# Schematic.net
KiCad netlist of a schematic drawn in EAGLE
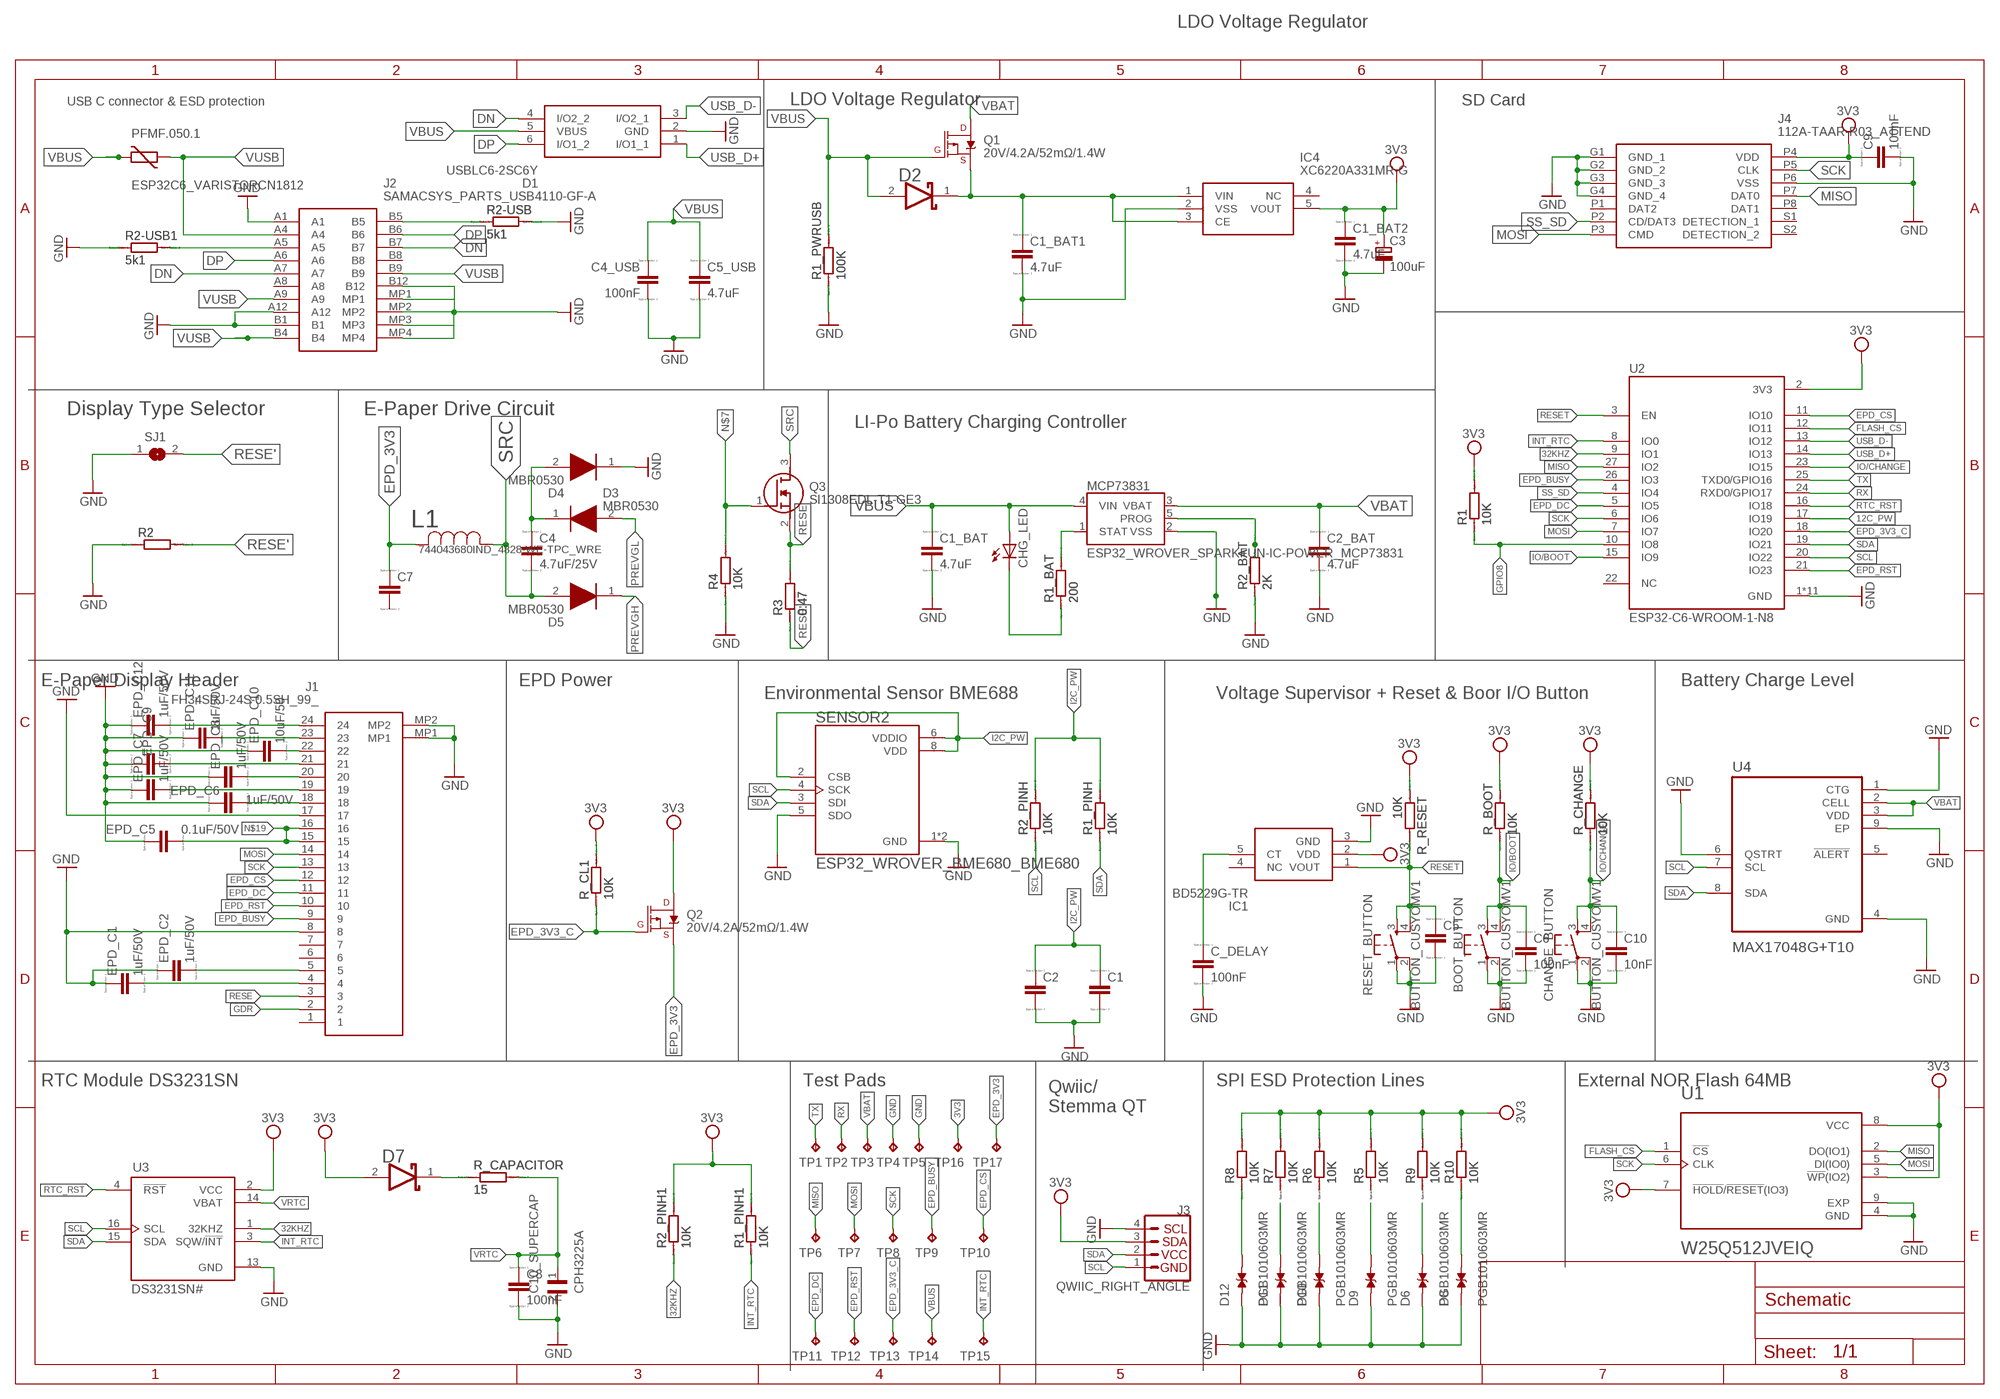
[diagram p0: schematic, sheet 1]

(export (version "E")
  (design (tool "Eeschema 10.0.6"))
  (components
    (comp (ref "BOOT_BUTTON")
      (value "BUTTON_CUSYOMV1")
      (footprint "eagle-import:MYBUTTON")
      (libsource (lib "eagle-import") (part "BUTTON_CUSYOMV1"))
    )
    (comp (ref "C1")
      (value "EAGLE-LTSPICE_CC0402")
      (footprint "eagle-import:EAGLE-LTSPICE_C0402")
      (libsource (lib "eagle-import") (part "EAGLE-LTSPICE_CC0402"))
    )
    (comp (ref "C1_BAT")
      (value "4.7uF")
      (footprint "eagle-import:EAGLE-LTSPICE_C0402")
      (libsource (lib "eagle-import") (part "EAGLE-LTSPICE_CC0402"))
    )
    (comp (ref "C1_BAT1")
      (value "4.7uF")
      (footprint "eagle-import:EAGLE-LTSPICE_C0402")
      (libsource (lib "eagle-import") (part "EAGLE-LTSPICE_CC0402"))
    )
    (comp (ref "C1_BAT2")
      (value "4.7uF")
      (footprint "eagle-import:EAGLE-LTSPICE_C0402")
      (libsource (lib "eagle-import") (part "EAGLE-LTSPICE_CC0402"))
    )
    (comp (ref "C2")
      (value "EAGLE-LTSPICE_CC0402")
      (footprint "eagle-import:EAGLE-LTSPICE_C0402")
      (libsource (lib "eagle-import") (part "EAGLE-LTSPICE_CC0402"))
    )
    (comp (ref "C2_BAT")
      (value "4.7uF")
      (footprint "eagle-import:EAGLE-LTSPICE_C0402")
      (libsource (lib "eagle-import") (part "EAGLE-LTSPICE_CC0402"))
    )
    (comp (ref "C3")
      (value "100uF")
      (footprint "eagle-import:RCL_CT3528")
      (libsource (lib "eagle-import") (part "RCL_CPOL-EUCT3528"))
    )
    (comp (ref "C4")
      (value "4.7uF/25V")
      (footprint "eagle-import:EAGLE-LTSPICE_C0402")
      (libsource (lib "eagle-import") (part "EAGLE-LTSPICE_CC0402"))
    )
    (comp (ref "C4_USB")
      (value "100nF")
      (footprint "eagle-import:EAGLE-LTSPICE_C0402")
      (libsource (lib "eagle-import") (part "EAGLE-LTSPICE_CC0402"))
    )
    (comp (ref "C5")
      (value "EAGLE-LTSPICE_CC0402")
      (footprint "eagle-import:EAGLE-LTSPICE_C0402")
      (libsource (lib "eagle-import") (part "EAGLE-LTSPICE_CC0402"))
    )
    (comp (ref "C5_USB")
      (value "4.7uF")
      (footprint "eagle-import:EAGLE-LTSPICE_C0402")
      (libsource (lib "eagle-import") (part "EAGLE-LTSPICE_CC0402"))
    )
    (comp (ref "C6")
      (value "100nF")
      (footprint "eagle-import:EAGLE-LTSPICE_C0402")
      (libsource (lib "eagle-import") (part "EAGLE-LTSPICE_CC0402"))
    )
    (comp (ref "C7")
      (value "EAGLE-LTSPICE_CC0402")
      (footprint "eagle-import:EAGLE-LTSPICE_C0402")
      (libsource (lib "eagle-import") (part "EAGLE-LTSPICE_CC0402"))
    )
    (comp (ref "C8")
      (value "100nF")
      (footprint "eagle-import:EAGLE-LTSPICE_C0402")
      (libsource (lib "eagle-import") (part "EAGLE-LTSPICE_CC0402"))
    )
    (comp (ref "C9")
      (value "100nF")
      (footprint "eagle-import:EAGLE-LTSPICE_C0402")
      (libsource (lib "eagle-import") (part "EAGLE-LTSPICE_CC0402"))
    )
    (comp (ref "C10")
      (value "10nF")
      (footprint "eagle-import:EAGLE-LTSPICE_C0402")
      (libsource (lib "eagle-import") (part "EAGLE-LTSPICE_CC0402"))
    )
    (comp (ref "C10_SUPERCAP")
      (value "CPH3225A")
      (footprint "eagle-import:CAPCP3225X100N")
      (fields (field (name "MF") "Seiko Instruments"))
      (libsource (lib "eagle-import") (part "CPH3225A"))
    )
    (comp (ref "CHANGE_BUTTON")
      (value "BUTTON_CUSYOMV1")
      (footprint "eagle-import:MYBUTTON")
      (libsource (lib "eagle-import") (part "BUTTON_CUSYOMV1"))
    )
    (comp (ref "CHG_LED")
      (value "ADAFRUIT_LEDCHIP-LED0603")
      (footprint "eagle-import:ADAFRUIT_CHIP-LED0603")
      (libsource (lib "eagle-import") (part "ADAFRUIT_LEDCHIP-LED0603"))
    )
    (comp (ref "C_DELAY")
      (value "100nF")
      (footprint "eagle-import:EAGLE-LTSPICE_C0402")
      (libsource (lib "eagle-import") (part "EAGLE-LTSPICE_CC0402"))
    )
    (comp (ref "D1")
      (value "USBLC6-2SC6Y")
      (footprint "eagle-import:SOT95P280X145-6N")
      (fields (field (name "MF") "STMicroelectronics"))
      (libsource (lib "eagle-import") (part "USBLC6-2SC6Y"))
    )
    (comp (ref "D2")
      (value "ESP32_WROVER_AVX---SD0805S020S1R0_AVX_SD0805S020S1R0_0_0AVX_SD0805S020S1R0_0_0")
      (footprint "eagle-import:ESP32_WROVER_AVX---SD0805S020S1R0_AVX_SD0805S020S1R0_0")
      (fields
        (field (name "DIGIKEY_PART_NUMBER") "478-7800-1-ND")
        (field (name "MF") "AVX")
        (field (name "MOUSER_PART_NUMBER") "581-SD0805S020S1R0")
      )
      (libsource (lib "eagle-import") (part "ESP32_WROVER_AVX---SD0805S020S1R0_AVX_SD0805S020S1R0_0_0AVX_SD0805S020S1R0_0_0"))
    )
    (comp (ref "D3")
      (value "MBR0530")
      (footprint "eagle-import:SOD3716X135N")
      (fields (field (name "MF") "ON Semiconductor"))
      (libsource (lib "eagle-import") (part "MBR0530"))
    )
    (comp (ref "D4")
      (value "MBR0530")
      (footprint "eagle-import:SOD3716X135N")
      (fields (field (name "MF") "ON Semiconductor"))
      (libsource (lib "eagle-import") (part "MBR0530"))
    )
    (comp (ref "D5")
      (value "MBR0530")
      (footprint "eagle-import:SOD3716X135N")
      (fields (field (name "MF") "ON Semiconductor"))
      (libsource (lib "eagle-import") (part "MBR0530"))
    )
    (comp (ref "D6")
      (value "PGB1010603MR")
      (footprint "eagle-import:DIOC1608X36N")
      (fields (field (name "MF") "Littelfuse Inc."))
      (libsource (lib "eagle-import") (part "PGB1010603MR"))
    )
    (comp (ref "D7")
      (value "ESP32_WROVER_AVX---SD0805S020S1R0_AVX_SD0805S020S1R0_0_0AVX_SD0805S020S1R0_0_0")
      (footprint "eagle-import:ESP32_WROVER_AVX---SD0805S020S1R0_AVX_SD0805S020S1R0_0")
      (fields
        (field (name "DIGIKEY_PART_NUMBER") "478-7800-1-ND")
        (field (name "MF") "AVX")
        (field (name "MOUSER_PART_NUMBER") "581-SD0805S020S1R0")
      )
      (libsource (lib "eagle-import") (part "ESP32_WROVER_AVX---SD0805S020S1R0_AVX_SD0805S020S1R0_0_0AVX_SD0805S020S1R0_0_0"))
    )
    (comp (ref "D8")
      (value "PGB1010603MR")
      (footprint "eagle-import:DIOC1608X36N")
      (fields (field (name "MF") "Littelfuse Inc."))
      (libsource (lib "eagle-import") (part "PGB1010603MR"))
    )
    (comp (ref "D9")
      (value "PGB1010603MR")
      (footprint "eagle-import:DIOC1608X36N")
      (fields (field (name "MF") "Littelfuse Inc."))
      (libsource (lib "eagle-import") (part "PGB1010603MR"))
    )
    (comp (ref "D10")
      (value "PGB1010603MR")
      (footprint "eagle-import:DIOC1608X36N")
      (fields (field (name "MF") "Littelfuse Inc."))
      (libsource (lib "eagle-import") (part "PGB1010603MR"))
    )
    (comp (ref "D11")
      (value "PGB1010603MR")
      (footprint "eagle-import:DIOC1608X36N")
      (fields (field (name "MF") "Littelfuse Inc."))
      (libsource (lib "eagle-import") (part "PGB1010603MR"))
    )
    (comp (ref "D12")
      (value "PGB1010603MR")
      (footprint "eagle-import:DIOC1608X36N")
      (fields (field (name "MF") "Littelfuse Inc."))
      (libsource (lib "eagle-import") (part "PGB1010603MR"))
    )
    (comp (ref "EPD_C1")
      (value "1uF/50V")
      (footprint "eagle-import:EAGLE-LTSPICE_C0402")
      (libsource (lib "eagle-import") (part "EAGLE-LTSPICE_CC0402"))
    )
    (comp (ref "EPD_C2")
      (value "1uF/50V")
      (footprint "eagle-import:EAGLE-LTSPICE_C0402")
      (libsource (lib "eagle-import") (part "EAGLE-LTSPICE_CC0402"))
    )
    (comp (ref "EPD_C5")
      (value "0.1uF/50V")
      (footprint "eagle-import:EAGLE-LTSPICE_C0402")
      (libsource (lib "eagle-import") (part "EAGLE-LTSPICE_CC0402"))
    )
    (comp (ref "EPD_C6")
      (value "1uF/50V")
      (footprint "eagle-import:EAGLE-LTSPICE_C0402")
      (libsource (lib "eagle-import") (part "EAGLE-LTSPICE_CC0402"))
    )
    (comp (ref "EPD_C7")
      (value "1uF/50V")
      (footprint "eagle-import:EAGLE-LTSPICE_C0402")
      (libsource (lib "eagle-import") (part "EAGLE-LTSPICE_CC0402"))
    )
    (comp (ref "EPD_C8")
      (value "1uF/50V")
      (footprint "eagle-import:EAGLE-LTSPICE_C0402")
      (libsource (lib "eagle-import") (part "EAGLE-LTSPICE_CC0402"))
    )
    (comp (ref "EPD_C9")
      (value "EAGLE-LTSPICE_CC0402")
      (footprint "eagle-import:EAGLE-LTSPICE_C0402")
      (libsource (lib "eagle-import") (part "EAGLE-LTSPICE_CC0402"))
    )
    (comp (ref "EPD_C10")
      (value "10uF/50")
      (footprint "eagle-import:EAGLE-LTSPICE_C0402")
      (libsource (lib "eagle-import") (part "EAGLE-LTSPICE_CC0402"))
    )
    (comp (ref "EPD_C11")
      (value "1uF/50V")
      (footprint "eagle-import:EAGLE-LTSPICE_C0402")
      (libsource (lib "eagle-import") (part "EAGLE-LTSPICE_CC0402"))
    )
    (comp (ref "EPD_C12")
      (value "1uF/50V")
      (footprint "eagle-import:EAGLE-LTSPICE_C0402")
      (libsource (lib "eagle-import") (part "EAGLE-LTSPICE_CC0402"))
    )
    (comp (ref "IC1")
      (value "BD5229G-TR")
      (footprint "eagle-import:SOT95P280X125-5N")
      (fields (field (name "MOUSER_PART_NUMBER") "755-BD5229G-TR"))
      (libsource (lib "eagle-import") (part "BD5229G-TR"))
    )
    (comp (ref "IC4")
      (value "XC6220A331MR-G")
      (footprint "eagle-import:SOT95P280X120-5N")
      (fields (field (name "MOUSER_PART_NUMBER") "865-XC6220A331MR-G"))
      (libsource (lib "eagle-import") (part "XC6220A331MR-G"))
    )
    (comp (ref "J1")
      (value "FH34SRJ-24S-0.5SH_99_")
      (footprint "eagle-import:FH34SRJ24S05SH99")
      (fields
        (field (name "MANUFACTURER_PART_NUMBER") "FH34SRJ-24S-0.5SH(99)")
        (field (name "MOUSER_PART_NUMBER") "798-FH34SRJ24S05SH99")
      )
      (libsource (lib "eagle-import") (part "FH34SRJ-24S-0.5SH_99_"))
    )
    (comp (ref "J2")
      (value "SAMACSYS_PARTS_USB4110-GF-A")
      (footprint "eagle-import:SAMACSYS_PARTS_USB4110GFA")
      (fields
        (field (name "MANUFACTURER_PART_NUMBER") "USB4110-GF-A")
        (field (name "MOUSER_PART_NUMBER") "640-USB4110-GF-A")
      )
      (libsource (lib "eagle-import") (part "SAMACSYS_PARTS_USB4110-GF-A"))
    )
    (comp (ref "J3")
      (value "QWIIC_RIGHT_ANGLE")
      (footprint "eagle-import:JST04_1MM_RA")
      (libsource (lib "eagle-import") (part "QWIIC_CONNECTORJS-1MM"))
    )
    (comp (ref "J4")
      (value "112A-TAAR-R03_ATTEND")
      (footprint "eagle-import:112ATAARR03ATTEND")
      (fields (field (name "MANUFACTURER_PART_NUMBER") "112A-TAAR-R03 ATTEND"))
      (libsource (lib "eagle-import") (part "112A-TAAR-R03_ATTEND"))
    )
    (comp (ref "L1")
      (value "744043680IND_4828-WE-TPC_WRE")
      (footprint "eagle-import:IND_4828-WE-TPC_WRE")
      (fields
        (field (name "MANUFACTURER_PART_NUMBER") "744043680")
        (field (name "COPYRIGHT") "Copyright (C) 2024 Ultra Librarian. All rights reserved.")
      )
      (libsource (lib "eagle-import") (part "744043680IND_4828-WE-TPC_WRE"))
    )
    (comp (ref "MCP73831")
      (value "ESP32_WROVER_SPARKFUN-IC-POWER_MCP73831")
      (footprint "eagle-import:ESP32_WROVER_SPARKFUN-IC-POWER_SOT23-5")
      (libsource (lib "eagle-import") (part "ESP32_WROVER_SPARKFUN-IC-POWER_MCP73831"))
    )
    (comp (ref "PFMF.050.1")
      (value "ESP32C6_VARISTORCN1812")
      (footprint "eagle-import:ESP32C6_VARISTOR_CT_CN1812")
      (libsource (lib "eagle-import") (part "ESP32C6_VARISTORCN1812"))
    )
    (comp (ref "Q1")
      (value "20V/4.2A/52mΩ/1.4W")
      (footprint "eagle-import:ESP32_WROVER_SPARKFUN-DISCRETESEMI_SOT23-3")
      (libsource (lib "eagle-import") (part "ESP32_WROVER_SPARKFUN-DISCRETESEMI_MOSFET_PCH-DMG2305UX-7"))
    )
    (comp (ref "Q2")
      (value "20V/4.2A/52mΩ/1.4W")
      (footprint "eagle-import:ESP32_WROVER_SPARKFUN-DISCRETESEMI_SOT23-3")
      (libsource (lib "eagle-import") (part "ESP32_WROVER_SPARKFUN-DISCRETESEMI_MOSFET_PCH-DMG2305UX-7"))
    )
    (comp (ref "Q3")
      (value "SI1308EDL-T1-GE3")
      (footprint "eagle-import:SOT65P210X110-3N")
      (fields (field (name "MF") "Vishay Siliconix"))
      (libsource (lib "eagle-import") (part "SI1308EDL-T1-GE3"))
    )
    (comp (ref "R1")
      (value "10K")
      (footprint "eagle-import:ESP32_WROVER_EAGLE-LTSPICE_R0402")
      (libsource (lib "eagle-import") (part "ESP32_WROVER_EAGLE-LTSPICE_RR0402"))
    )
    (comp (ref "R1_BAT")
      (value "200")
      (footprint "eagle-import:ESP32_WROVER_EAGLE-LTSPICE_R0402")
      (libsource (lib "eagle-import") (part "ESP32_WROVER_EAGLE-LTSPICE_RR0402"))
    )
    (comp (ref "R1_PINH")
      (value "10K")
      (footprint "eagle-import:ESP32_WROVER_EAGLE-LTSPICE_R0402")
      (libsource (lib "eagle-import") (part "ESP32_WROVER_EAGLE-LTSPICE_RR0402"))
    )
    (comp (ref "R1_PINH1")
      (value "10K")
      (footprint "eagle-import:ESP32_WROVER_EAGLE-LTSPICE_R0402")
      (libsource (lib "eagle-import") (part "ESP32_WROVER_EAGLE-LTSPICE_RR0402"))
    )
    (comp (ref "R1_PWRUSB")
      (value "100K")
      (footprint "eagle-import:ESP32_WROVER_EAGLE-LTSPICE_R0402")
      (libsource (lib "eagle-import") (part "ESP32_WROVER_EAGLE-LTSPICE_RR0402"))
    )
    (comp (ref "R2")
      (value "ESP32_WROVER_EAGLE-LTSPICE_RR0402")
      (footprint "eagle-import:ESP32_WROVER_EAGLE-LTSPICE_R0402")
      (libsource (lib "eagle-import") (part "ESP32_WROVER_EAGLE-LTSPICE_RR0402"))
    )
    (comp (ref "R2-USB")
      (value "5k1")
      (footprint "eagle-import:ESP32_WROVER_EAGLE-LTSPICE_R0402")
      (libsource (lib "eagle-import") (part "ESP32_WROVER_EAGLE-LTSPICE_RR0402"))
    )
    (comp (ref "R2-USB1")
      (value "5k1")
      (footprint "eagle-import:ESP32_WROVER_EAGLE-LTSPICE_R0402")
      (libsource (lib "eagle-import") (part "ESP32_WROVER_EAGLE-LTSPICE_RR0402"))
    )
    (comp (ref "R2_BAT")
      (value "2K")
      (footprint "eagle-import:ESP32_WROVER_EAGLE-LTSPICE_R0402")
      (libsource (lib "eagle-import") (part "ESP32_WROVER_EAGLE-LTSPICE_RR0402"))
    )
    (comp (ref "R2_PINH")
      (value "10K")
      (footprint "eagle-import:ESP32_WROVER_EAGLE-LTSPICE_R0402")
      (libsource (lib "eagle-import") (part "ESP32_WROVER_EAGLE-LTSPICE_RR0402"))
    )
    (comp (ref "R2_PINH1")
      (value "10K")
      (footprint "eagle-import:ESP32_WROVER_EAGLE-LTSPICE_R0402")
      (libsource (lib "eagle-import") (part "ESP32_WROVER_EAGLE-LTSPICE_RR0402"))
    )
    (comp (ref "R3")
      (value "0.47")
      (footprint "eagle-import:ESP32_WROVER_EAGLE-LTSPICE_R0402")
      (libsource (lib "eagle-import") (part "ESP32_WROVER_EAGLE-LTSPICE_RR0402"))
    )
    (comp (ref "R4")
      (value "10K")
      (footprint "eagle-import:ESP32_WROVER_EAGLE-LTSPICE_R0402")
      (libsource (lib "eagle-import") (part "ESP32_WROVER_EAGLE-LTSPICE_RR0402"))
    )
    (comp (ref "R5")
      (value "10K")
      (footprint "eagle-import:ESP32_WROVER_EAGLE-LTSPICE_R0402")
      (libsource (lib "eagle-import") (part "ESP32_WROVER_EAGLE-LTSPICE_RR0402"))
    )
    (comp (ref "R6")
      (value "10K")
      (footprint "eagle-import:ESP32_WROVER_EAGLE-LTSPICE_R0402")
      (libsource (lib "eagle-import") (part "ESP32_WROVER_EAGLE-LTSPICE_RR0402"))
    )
    (comp (ref "R7")
      (value "10K")
      (footprint "eagle-import:ESP32_WROVER_EAGLE-LTSPICE_R0402")
      (libsource (lib "eagle-import") (part "ESP32_WROVER_EAGLE-LTSPICE_RR0402"))
    )
    (comp (ref "R8")
      (value "10K")
      (footprint "eagle-import:ESP32_WROVER_EAGLE-LTSPICE_R0402")
      (libsource (lib "eagle-import") (part "ESP32_WROVER_EAGLE-LTSPICE_RR0402"))
    )
    (comp (ref "R9")
      (value "10K")
      (footprint "eagle-import:ESP32_WROVER_EAGLE-LTSPICE_R0402")
      (libsource (lib "eagle-import") (part "ESP32_WROVER_EAGLE-LTSPICE_RR0402"))
    )
    (comp (ref "R10")
      (value "10K")
      (footprint "eagle-import:ESP32_WROVER_EAGLE-LTSPICE_R0402")
      (libsource (lib "eagle-import") (part "ESP32_WROVER_EAGLE-LTSPICE_RR0402"))
    )
    (comp (ref "RESET_BUTTON")
      (value "BUTTON_CUSYOMV1")
      (footprint "eagle-import:MYBUTTON")
      (libsource (lib "eagle-import") (part "BUTTON_CUSYOMV1"))
    )
    (comp (ref "R_BOOT")
      (value "10K")
      (footprint "eagle-import:ESP32_WROVER_EAGLE-LTSPICE_R0402")
      (libsource (lib "eagle-import") (part "ESP32_WROVER_EAGLE-LTSPICE_RR0402"))
    )
    (comp (ref "R_CAPACITOR")
      (value "15")
      (footprint "eagle-import:ESP32_WROVER_EAGLE-LTSPICE_R0402")
      (libsource (lib "eagle-import") (part "ESP32_WROVER_EAGLE-LTSPICE_RR0402"))
    )
    (comp (ref "R_CHANGE")
      (value "10K")
      (footprint "eagle-import:ESP32_WROVER_EAGLE-LTSPICE_R0402")
      (libsource (lib "eagle-import") (part "ESP32_WROVER_EAGLE-LTSPICE_RR0402"))
    )
    (comp (ref "R_CL1")
      (value "10K")
      (footprint "eagle-import:ESP32_WROVER_EAGLE-LTSPICE_R0402")
      (libsource (lib "eagle-import") (part "ESP32_WROVER_EAGLE-LTSPICE_RR0402"))
    )
    (comp (ref "R_RESET")
      (value "10K")
      (footprint "eagle-import:ESP32_WROVER_EAGLE-LTSPICE_R0402")
      (libsource (lib "eagle-import") (part "ESP32_WROVER_EAGLE-LTSPICE_RR0402"))
    )
    (comp (ref "SENSOR2")
      (value "ESP32_WROVER_BME680_BME680")
      (footprint "eagle-import:ESP32_WROVER_BME680_PSON80P300X300X100-8N")
      (fields (field (name "MF") "Bosch Sensortec") (field (name "MP") "BME680"))
      (libsource (lib "eagle-import") (part "ESP32_WROVER_BME680_BME680"))
    )
    (comp (ref "SJ1") (value "SJ") (footprint "eagle-import:SJ") (libsource (lib "eagle-import") (part "SJ")))
    (comp (ref "TP1")
      (value "TPTP20R")
      (footprint "eagle-import:TP20R")
      (libsource (lib "eagle-import") (part "TPTP20R"))
    )
    (comp (ref "TP2")
      (value "TPTP20R")
      (footprint "eagle-import:TP20R")
      (libsource (lib "eagle-import") (part "TPTP20R"))
    )
    (comp (ref "TP3")
      (value "TPTP20R")
      (footprint "eagle-import:TP20R")
      (libsource (lib "eagle-import") (part "TPTP20R"))
    )
    (comp (ref "TP4")
      (value "TPTP20R")
      (footprint "eagle-import:TP20R")
      (libsource (lib "eagle-import") (part "TPTP20R"))
    )
    (comp (ref "TP5")
      (value "TPTP20R")
      (footprint "eagle-import:TP20R")
      (libsource (lib "eagle-import") (part "TPTP20R"))
    )
    (comp (ref "TP6")
      (value "TPTP20R")
      (footprint "eagle-import:TP20R")
      (libsource (lib "eagle-import") (part "TPTP20R"))
    )
    (comp (ref "TP7")
      (value "TPTP20R")
      (footprint "eagle-import:TP20R")
      (libsource (lib "eagle-import") (part "TPTP20R"))
    )
    (comp (ref "TP8")
      (value "TPTP20R")
      (footprint "eagle-import:TP20R")
      (libsource (lib "eagle-import") (part "TPTP20R"))
    )
    (comp (ref "TP9")
      (value "TPTP20R")
      (footprint "eagle-import:TP20R")
      (libsource (lib "eagle-import") (part "TPTP20R"))
    )
    (comp (ref "TP10")
      (value "TPTP20R")
      (footprint "eagle-import:TP20R")
      (libsource (lib "eagle-import") (part "TPTP20R"))
    )
    (comp (ref "TP11")
      (value "TPTP20R")
      (footprint "eagle-import:TP20R")
      (libsource (lib "eagle-import") (part "TPTP20R"))
    )
    (comp (ref "TP12")
      (value "TPTP20R")
      (footprint "eagle-import:TP20R")
      (libsource (lib "eagle-import") (part "TPTP20R"))
    )
    (comp (ref "TP13")
      (value "TPTP20R")
      (footprint "eagle-import:TP20R")
      (libsource (lib "eagle-import") (part "TPTP20R"))
    )
    (comp (ref "TP14")
      (value "TPTP20R")
      (footprint "eagle-import:TP20R")
      (libsource (lib "eagle-import") (part "TPTP20R"))
    )
    (comp (ref "TP15")
      (value "TPTP20R")
      (footprint "eagle-import:TP20R")
      (libsource (lib "eagle-import") (part "TPTP20R"))
    )
    (comp (ref "TP16")
      (value "TPTP20R")
      (footprint "eagle-import:TP20R")
      (libsource (lib "eagle-import") (part "TPTP20R"))
    )
    (comp (ref "TP17")
      (value "TPTP20R")
      (footprint "eagle-import:TP20R")
      (libsource (lib "eagle-import") (part "TPTP20R"))
    )
    (comp (ref "U1")
      (value "W25Q512JVEIQ")
      (footprint "eagle-import:SON127P600X800X80-9N")
      (fields (field (name "MF") "Winbond Electronics"))
      (libsource (lib "eagle-import") (part "W25Q512JVEIQ"))
    )
    (comp (ref "U2")
      (value "ESP32-C6-WROOM-1-N8")
      (footprint "eagle-import:XCVR_ESP32-C6-WROOM-1-N8")
      (fields (field (name "MF") "Espressif Systems"))
      (libsource (lib "eagle-import") (part "ESP32-C6-WROOM-1-N8"))
    )
    (comp (ref "U3")
      (value "DS3231SN#")
      (footprint "eagle-import:SOIC127P1032X265-16N")
      (fields (field (name "MF") "Analog Devices"))
      (libsource (lib "eagle-import") (part "DS3231SN#"))
    )
    (comp (ref "U4")
      (value "MAX17048G+T10")
      (footprint "eagle-import:SON50P200X200X80-9N")
      (fields (field (name "MF") "Analog Devices"))
      (libsource (lib "eagle-import") (part "MAX17048G+T10"))
    )
  )
  (nets
    (net (code "1") (name "3V3") (class "Default")
      (node (ref "C1_BAT2") (pin "1") (pinfunction "1_1") (pintype "passive"))
      (node (ref "C3") (pin "+") (pinfunction "+_+") (pintype "passive"))
      (node (ref "C9") (pin "1") (pinfunction "1_1") (pintype "passive"))
      (node (ref "D7") (pin "2") (pinfunction "ANODE_2") (pintype "bidirectional"))
      (node (ref "IC1") (pin "2") (pinfunction "VDD_2") (pintype "bidirectional"))
      (node (ref "IC4") (pin "5") (pinfunction "VOUT_5") (pintype "bidirectional"))
      (node (ref "J3") (pin "3") (pinfunction "3_3") (pintype "passive"))
      (node (ref "J4") (pin "P4") (pinfunction "VDD_P4") (pintype "bidirectional"))
      (node (ref "Q2") (pin "3") (pinfunction "D_3") (pintype "bidirectional"))
      (node (ref "R1") (pin "2") (pinfunction "2_2") (pintype "passive"))
      (node (ref "R10") (pin "2") (pinfunction "2_2") (pintype "passive"))
      (node (ref "R1_PINH1") (pin "2") (pinfunction "2_2") (pintype "passive"))
      (node (ref "R2_PINH1") (pin "2") (pinfunction "2_2") (pintype "passive"))
      (node (ref "R5") (pin "2") (pinfunction "2_2") (pintype "passive"))
      (node (ref "R6") (pin "2") (pinfunction "2_2") (pintype "passive"))
      (node (ref "R7") (pin "2") (pinfunction "2_2") (pintype "passive"))
      (node (ref "R8") (pin "2") (pinfunction "2_2") (pintype "passive"))
      (node (ref "R9") (pin "2") (pinfunction "2_2") (pintype "passive"))
      (node (ref "R_BOOT") (pin "2") (pinfunction "2_2") (pintype "passive"))
      (node (ref "R_CHANGE") (pin "2") (pinfunction "2_2") (pintype "passive"))
      (node (ref "R_CL1") (pin "2") (pinfunction "2_2") (pintype "passive"))
      (node (ref "R_RESET") (pin "1") (pinfunction "1_1") (pintype "passive"))
      (node (ref "TP16") (pin "TP") (pinfunction "TP_TP") (pintype "input"))
      (node (ref "U1") (pin "3") (pinfunction "~{WP}(IO2)_3") (pintype "bidirectional"))
      (node (ref "U1") (pin "7") (pinfunction "~{HOLD}/~{RESET}(IO3)_7") (pintype "bidirectional"))
      (node (ref "U1") (pin "8") (pinfunction "VCC_8") (pintype "power_in"))
      (node (ref "U2") (pin "2") (pinfunction "3V3_2") (pintype "power_in"))
      (node (ref "U3") (pin "2") (pinfunction "VCC_2") (pintype "power_in"))
    )
    (net (code "2") (name "12C_PW") (class "Default")
      (node (ref "U2") (pin "17") (pinfunction "IO19_17") (pintype "bidirectional"))
    )
    (net (code "3") (name "32KHZ") (class "Default")
      (node (ref "R2_PINH1") (pin "1") (pinfunction "1_1") (pintype "passive"))
      (node (ref "U2") (pin "9") (pinfunction "IO1_9") (pintype "bidirectional"))
      (node (ref "U3") (pin "1") (pinfunction "32KHZ_1") (pintype "output"))
    )
    (net (code "4") (name "DN") (class "Default")
      (node (ref "D1") (pin "4") (pinfunction "I/O2_2_4") (pintype "bidirectional"))
      (node (ref "J2") (pin "A7") (pinfunction "A7_A7") (pintype "bidirectional"))
      (node (ref "J2") (pin "B7") (pinfunction "B7_B7") (pintype "bidirectional"))
    )
    (net (code "5") (name "DP") (class "Default")
      (node (ref "D1") (pin "6") (pinfunction "I/O1_2_6") (pintype "bidirectional"))
      (node (ref "J2") (pin "A6") (pinfunction "A6_A6") (pintype "bidirectional"))
      (node (ref "J2") (pin "B6") (pinfunction "B6_B6") (pintype "bidirectional"))
    )
    (net (code "6") (name "EPD_3V3") (class "Default")
      (node (ref "C7") (pin "1") (pinfunction "1_1") (pintype "passive"))
      (node (ref "L1") (pin "2") (pinfunction "2_2") (pintype "passive"))
      (node (ref "Q2") (pin "2") (pinfunction "S_2") (pintype "bidirectional"))
      (node (ref "TP17") (pin "TP") (pinfunction "TP_TP") (pintype "input"))
    )
    (net (code "7") (name "EPD_3V3_C") (class "Default")
      (node (ref "Q2") (pin "1") (pinfunction "G_1") (pintype "bidirectional"))
      (node (ref "R_CL1") (pin "1") (pinfunction "1_1") (pintype "passive"))
      (node (ref "TP13") (pin "TP") (pinfunction "TP_TP") (pintype "input"))
      (node (ref "U2") (pin "18") (pinfunction "IO20_18") (pintype "bidirectional"))
    )
    (net (code "8") (name "EPD_BUSY") (class "Default")
      (node (ref "J1") (pin "9") (pinfunction "9_9") (pintype "bidirectional"))
      (node (ref "TP9") (pin "TP") (pinfunction "TP_TP") (pintype "input"))
      (node (ref "U2") (pin "26") (pinfunction "IO3_26") (pintype "bidirectional"))
    )
    (net (code "9") (name "EPD_CS") (class "Default")
      (node (ref "J1") (pin "12") (pinfunction "12_12") (pintype "bidirectional"))
      (node (ref "TP10") (pin "TP") (pinfunction "TP_TP") (pintype "input"))
      (node (ref "U2") (pin "11") (pinfunction "IO10_11") (pintype "bidirectional"))
    )
    (net (code "10") (name "EPD_DC") (class "Default")
      (node (ref "J1") (pin "11") (pinfunction "11_11") (pintype "bidirectional"))
      (node (ref "TP11") (pin "TP") (pinfunction "TP_TP") (pintype "input"))
      (node (ref "U2") (pin "5") (pinfunction "IO5_5") (pintype "bidirectional"))
    )
    (net (code "11") (name "EPD_RST") (class "Default")
      (node (ref "J1") (pin "10") (pinfunction "10_10") (pintype "bidirectional"))
      (node (ref "TP12") (pin "TP") (pinfunction "TP_TP") (pintype "input"))
      (node (ref "U2") (pin "21") (pinfunction "IO23_21") (pintype "bidirectional"))
    )
    (net (code "12") (name "FLASH_CS") (class "Default")
      (node (ref "U1") (pin "1") (pinfunction "~{CS}_1") (pintype "input"))
      (node (ref "U2") (pin "12") (pinfunction "IO11_12") (pintype "bidirectional"))
    )
    (net (code "13") (name "GDR") (class "Default")
      (node (ref "J1") (pin "2") (pinfunction "2_2") (pintype "bidirectional"))
    )
    (net (code "14") (name "GND") (class "Default")
      (node (ref "BOOT_BUTTON") (pin "1") (pinfunction "1_1") (pintype "passive"))
      (node (ref "BOOT_BUTTON") (pin "2") (pinfunction "2_2") (pintype "passive"))
      (node (ref "C1") (pin "2") (pinfunction "2_2") (pintype "passive"))
      (node (ref "C10") (pin "2") (pinfunction "2_2") (pintype "passive"))
      (node (ref "C10_SUPERCAP") (pin "2") (pinfunction "2_2") (pintype "passive"))
      (node (ref "C1_BAT") (pin "2") (pinfunction "2_2") (pintype "passive"))
      (node (ref "C1_BAT1") (pin "2") (pinfunction "2_2") (pintype "passive"))
      (node (ref "C1_BAT2") (pin "2") (pinfunction "2_2") (pintype "passive"))
      (node (ref "C2") (pin "2") (pinfunction "2_2") (pintype "passive"))
      (node (ref "C2_BAT") (pin "2") (pinfunction "2_2") (pintype "passive"))
      (node (ref "C3") (pin "-") (pinfunction "-_-") (pintype "passive"))
      (node (ref "C4_USB") (pin "2") (pinfunction "2_2") (pintype "passive"))
      (node (ref "C5") (pin "2") (pinfunction "2_2") (pintype "passive"))
      (node (ref "C5_USB") (pin "2") (pinfunction "2_2") (pintype "passive"))
      (node (ref "C6") (pin "2") (pinfunction "2_2") (pintype "passive"))
      (node (ref "C8") (pin "2") (pinfunction "2_2") (pintype "passive"))
      (node (ref "C9") (pin "2") (pinfunction "2_2") (pintype "passive"))
      (node (ref "CHANGE_BUTTON") (pin "1") (pinfunction "1_1") (pintype "passive"))
      (node (ref "CHANGE_BUTTON") (pin "2") (pinfunction "2_2") (pintype "passive"))
      (node (ref "C_DELAY") (pin "2") (pinfunction "2_2") (pintype "passive"))
      (node (ref "D1") (pin "2") (pinfunction "GND_2") (pintype "bidirectional"))
      (node (ref "D10") (pin "1") (pinfunction "1_1") (pintype "passive"))
      (node (ref "D11") (pin "1") (pinfunction "1_1") (pintype "passive"))
      (node (ref "D12") (pin "1") (pinfunction "1_1") (pintype "passive"))
      (node (ref "D4") (pin "1") (pinfunction "K_1") (pintype "bidirectional"))
      (node (ref "D6") (pin "1") (pinfunction "1_1") (pintype "passive"))
      (node (ref "D8") (pin "1") (pinfunction "1_1") (pintype "passive"))
      (node (ref "D9") (pin "1") (pinfunction "1_1") (pintype "passive"))
      (node (ref "EPD_C1") (pin "1") (pinfunction "1_1") (pintype "passive"))
      (node (ref "EPD_C10") (pin "1") (pinfunction "1_1") (pintype "passive"))
      (node (ref "EPD_C11") (pin "1") (pinfunction "1_1") (pintype "passive"))
      (node (ref "EPD_C12") (pin "1") (pinfunction "1_1") (pintype "passive"))
      (node (ref "EPD_C2") (pin "1") (pinfunction "1_1") (pintype "passive"))
      (node (ref "EPD_C5") (pin "1") (pinfunction "1_1") (pintype "passive"))
      (node (ref "EPD_C6") (pin "1") (pinfunction "1_1") (pintype "passive"))
      (node (ref "EPD_C7") (pin "1") (pinfunction "1_1") (pintype "passive"))
      (node (ref "EPD_C8") (pin "1") (pinfunction "1_1") (pintype "passive"))
      (node (ref "EPD_C9") (pin "1") (pinfunction "1_1") (pintype "passive"))
      (node (ref "IC1") (pin "3") (pinfunction "GND_3") (pintype "bidirectional"))
      (node (ref "IC4") (pin "2") (pinfunction "VSS_2") (pintype "bidirectional"))
      (node (ref "J1") (pin "17") (pinfunction "17_17") (pintype "bidirectional"))
      (node (ref "J1") (pin "8") (pinfunction "8_8") (pintype "bidirectional"))
      (node (ref "J1") (pin "MP1") (pinfunction "MP1_MP1") (pintype "bidirectional"))
      (node (ref "J1") (pin "MP2") (pinfunction "MP2_MP2") (pintype "bidirectional"))
      (node (ref "J2") (pin "A1") (pinfunction "A1_A1") (pintype "bidirectional"))
      (node (ref "J2") (pin "A12") (pinfunction "A12_A12") (pintype "bidirectional"))
      (node (ref "J2") (pin "B1") (pinfunction "B1_B1") (pintype "bidirectional"))
      (node (ref "J2") (pin "B12") (pinfunction "B12_B12") (pintype "bidirectional"))
      (node (ref "J2") (pin "MP1") (pinfunction "MP1_MP1") (pintype "bidirectional"))
      (node (ref "J2") (pin "MP2") (pinfunction "MP2_MP2") (pintype "bidirectional"))
      (node (ref "J2") (pin "MP3") (pinfunction "MP3_MP3") (pintype "bidirectional"))
      (node (ref "J2") (pin "MP4") (pinfunction "MP4_MP4") (pintype "bidirectional"))
      (node (ref "J3") (pin "4") (pinfunction "4_4") (pintype "passive"))
      (node (ref "J4") (pin "G1") (pinfunction "GND_1_G1") (pintype "bidirectional"))
      (node (ref "J4") (pin "G2") (pinfunction "GND_2_G2") (pintype "bidirectional"))
      (node (ref "J4") (pin "G3") (pinfunction "GND_3_G3") (pintype "bidirectional"))
      (node (ref "J4") (pin "G4") (pinfunction "GND_4_G4") (pintype "bidirectional"))
      (node (ref "J4") (pin "P6") (pinfunction "VSS_P6") (pintype "bidirectional"))
      (node (ref "MCP73831") (pin "2") (pinfunction "VSS_2") (pintype "power_in"))
      (node (ref "R1_PWRUSB") (pin "1") (pinfunction "1_1") (pintype "passive"))
      (node (ref "R2") (pin "1") (pinfunction "1_1") (pintype "passive"))
      (node (ref "R2-USB") (pin "2") (pinfunction "2_2") (pintype "passive"))
      (node (ref "R2-USB1") (pin "1") (pinfunction "1_1") (pintype "passive"))
      (node (ref "R2_BAT") (pin "1") (pinfunction "1_1") (pintype "passive"))
      (node (ref "R4") (pin "1") (pinfunction "1_1") (pintype "passive"))
      (node (ref "RESET_BUTTON") (pin "1") (pinfunction "1_1") (pintype "passive"))
      (node (ref "RESET_BUTTON") (pin "2") (pinfunction "2_2") (pintype "passive"))
      (node (ref "SENSOR2") (pin "1") (pinfunction "GND_1") (pintype "power_in"))
      (node (ref "SENSOR2") (pin "5") (pinfunction "SDO_5") (pintype "bidirectional"))
      (node (ref "SENSOR2") (pin "7") (pinfunction "GND_7") (pintype "power_in"))
      (node (ref "SJ1") (pin "1") (pinfunction "1_1") (pintype "passive"))
      (node (ref "TP4") (pin "TP") (pinfunction "TP_TP") (pintype "input"))
      (node (ref "TP5") (pin "TP") (pinfunction "TP_TP") (pintype "input"))
      (node (ref "U1") (pin "4") (pinfunction "GND_4") (pintype "power_in"))
      (node (ref "U1") (pin "9") (pinfunction "EXP_9") (pintype "passive"))
      (node (ref "U2") (pin "1") (pinfunction "GND_1") (pintype "power_in"))
      (node (ref "U2") (pin "28") (pinfunction "GND_28") (pintype "power_in"))
      (node (ref "U2") (pin "29_1") (pinfunction "GND_29_1") (pintype "power_in"))
      (node (ref "U2") (pin "29_2") (pinfunction "GND_29_2") (pintype "power_in"))
      (node (ref "U2") (pin "29_3") (pinfunction "GND_29_3") (pintype "power_in"))
      (node (ref "U2") (pin "29_4") (pinfunction "GND_29_4") (pintype "power_in"))
      (node (ref "U2") (pin "29_5") (pinfunction "GND_29_5") (pintype "power_in"))
      (node (ref "U2") (pin "29_6") (pinfunction "GND_29_6") (pintype "power_in"))
      (node (ref "U2") (pin "29_7") (pinfunction "GND_29_7") (pintype "power_in"))
      (node (ref "U2") (pin "29_8") (pinfunction "GND_29_8") (pintype "power_in"))
      (node (ref "U2") (pin "29_9") (pinfunction "GND_29_9") (pintype "power_in"))
      (node (ref "U3") (pin "13") (pinfunction "GND_13") (pintype "power_in"))
      (node (ref "U4") (pin "1") (pinfunction "CTG_1") (pintype "power_in"))
      (node (ref "U4") (pin "4") (pinfunction "GND_4") (pintype "power_in"))
      (node (ref "U4") (pin "6") (pinfunction "QSTRT_6") (pintype "input"))
      (node (ref "U4") (pin "9") (pinfunction "EP_9") (pintype "power_in"))
    )
    (net (code "15") (name "GPIO8") (class "Default")
      (node (ref "R1") (pin "1") (pinfunction "1_1") (pintype "passive"))
      (node (ref "U2") (pin "10") (pinfunction "IO8_10") (pintype "bidirectional"))
    )
    (net (code "16") (name "I2C_PW") (class "Default")
      (node (ref "C1") (pin "1") (pinfunction "1_1") (pintype "passive"))
      (node (ref "C2") (pin "1") (pinfunction "1_1") (pintype "passive"))
      (node (ref "R1_PINH") (pin "2") (pinfunction "2_2") (pintype "passive"))
      (node (ref "R2_PINH") (pin "2") (pinfunction "2_2") (pintype "passive"))
      (node (ref "SENSOR2") (pin "2") (pinfunction "CSB_2") (pintype "input"))
      (node (ref "SENSOR2") (pin "6") (pinfunction "VDDIO_6") (pintype "power_in"))
      (node (ref "SENSOR2") (pin "8") (pinfunction "VDD_8") (pintype "power_in"))
    )
    (net (code "17") (name "INT_RTC") (class "Default")
      (node (ref "R1_PINH1") (pin "1") (pinfunction "1_1") (pintype "passive"))
      (node (ref "TP15") (pin "TP") (pinfunction "TP_TP") (pintype "input"))
      (node (ref "U2") (pin "8") (pinfunction "IO0_8") (pintype "bidirectional"))
      (node (ref "U3") (pin "3") (pinfunction "SQW/~{INT}_3") (pintype "output"))
    )
    (net (code "18") (name "IO{slash}BOOT") (class "Default")
      (node (ref "BOOT_BUTTON") (pin "3") (pinfunction "3_3") (pintype "passive"))
      (node (ref "BOOT_BUTTON") (pin "4") (pinfunction "4_4") (pintype "passive"))
      (node (ref "C6") (pin "1") (pinfunction "1_1") (pintype "passive"))
      (node (ref "R_BOOT") (pin "1") (pinfunction "1_1") (pintype "passive"))
      (node (ref "U2") (pin "15") (pinfunction "IO9_15") (pintype "bidirectional"))
    )
    (net (code "19") (name "IO{slash}CHANGE") (class "Default")
      (node (ref "C10") (pin "1") (pinfunction "1_1") (pintype "passive"))
      (node (ref "CHANGE_BUTTON") (pin "3") (pinfunction "3_3") (pintype "passive"))
      (node (ref "CHANGE_BUTTON") (pin "4") (pinfunction "4_4") (pintype "passive"))
      (node (ref "R_CHANGE") (pin "1") (pinfunction "1_1") (pintype "passive"))
      (node (ref "U2") (pin "23") (pinfunction "IO15_23") (pintype "bidirectional"))
    )
    (net (code "20") (name "MISO") (class "Default")
      (node (ref "J4") (pin "P7") (pinfunction "DAT0_P7") (pintype "bidirectional"))
      (node (ref "TP6") (pin "TP") (pinfunction "TP_TP") (pintype "input"))
      (node (ref "U1") (pin "2") (pinfunction "DO(IO1)_2") (pintype "bidirectional"))
      (node (ref "U2") (pin "27") (pinfunction "IO2_27") (pintype "bidirectional"))
    )
    (net (code "21") (name "MOSI") (class "Default")
      (node (ref "J1") (pin "14") (pinfunction "14_14") (pintype "bidirectional"))
      (node (ref "J4") (pin "P3") (pinfunction "CMD_P3") (pintype "bidirectional"))
      (node (ref "TP7") (pin "TP") (pinfunction "TP_TP") (pintype "input"))
      (node (ref "U1") (pin "5") (pinfunction "DI(IO0)_5") (pintype "bidirectional"))
      (node (ref "U2") (pin "7") (pinfunction "IO7_7") (pintype "bidirectional"))
    )
    (net (code "22") (name "N$7") (class "Default")
      (node (ref "Q3") (pin "1") (pinfunction "G_1") (pintype "bidirectional"))
      (node (ref "R4") (pin "2") (pinfunction "2_2") (pintype "passive"))
    )
    (net (code "23") (name "N$19") (class "Default")
      (node (ref "EPD_C5") (pin "2") (pinfunction "2_2") (pintype "passive"))
      (node (ref "J1") (pin "15") (pinfunction "15_15") (pintype "bidirectional"))
      (node (ref "J1") (pin "16") (pinfunction "16_16") (pintype "bidirectional"))
    )
    (net (code "24") (name "Net-(CHG_LED-PadC)") (class "Default")
      (node (ref "CHG_LED") (pin "C") (pinfunction "C_C") (pintype "passive"))
      (node (ref "R1_BAT") (pin "1") (pinfunction "1_1") (pintype "passive"))
    )
    (net (code "25") (name "Net-(D2-CATHODE)") (class "Default")
      (node (ref "C1_BAT1") (pin "1") (pinfunction "1_1") (pintype "passive"))
      (node (ref "D2") (pin "1") (pinfunction "CATHODE_1") (pintype "bidirectional"))
      (node (ref "IC4") (pin "1") (pinfunction "VIN_1") (pintype "bidirectional"))
      (node (ref "IC4") (pin "3") (pinfunction "CE_3") (pintype "bidirectional"))
      (node (ref "Q1") (pin "2") (pinfunction "S_2") (pintype "bidirectional"))
    )
    (net (code "26") (name "Net-(D3-K)") (class "Default")
      (node (ref "C4") (pin "1") (pinfunction "1_1") (pintype "passive"))
      (node (ref "D3") (pin "1") (pinfunction "K_1") (pintype "bidirectional"))
      (node (ref "D4") (pin "2") (pinfunction "A_2") (pintype "bidirectional"))
    )
    (net (code "27") (name "Net-(D7-CATHODE)") (class "Default")
      (node (ref "D7") (pin "1") (pinfunction "CATHODE_1") (pintype "bidirectional"))
      (node (ref "R_CAPACITOR") (pin "1") (pinfunction "1_1") (pintype "passive"))
    )
    (net (code "28") (name "Net-(D8-Pad2)") (class "Default")
      (node (ref "D8") (pin "2") (pinfunction "2_2") (pintype "passive"))
      (node (ref "R10") (pin "1") (pinfunction "1_1") (pintype "passive"))
    )
    (net (code "29") (name "Net-(D12-Pad2)") (class "Default")
      (node (ref "D12") (pin "2") (pinfunction "2_2") (pintype "passive"))
      (node (ref "R8") (pin "1") (pinfunction "1_1") (pintype "passive"))
    )
    (net (code "30") (name "Net-(EPD_C1-Pad2)") (class "Default")
      (node (ref "EPD_C1") (pin "2") (pinfunction "2_2") (pintype "passive"))
      (node (ref "J1") (pin "4") (pinfunction "4_4") (pintype "bidirectional"))
    )
    (net (code "31") (name "Net-(EPD_C2-Pad2)") (class "Default")
      (node (ref "EPD_C2") (pin "2") (pinfunction "2_2") (pintype "passive"))
      (node (ref "J1") (pin "5") (pinfunction "5_5") (pintype "bidirectional"))
    )
    (net (code "32") (name "Net-(EPD_C6-Pad2)") (class "Default")
      (node (ref "EPD_C6") (pin "2") (pinfunction "2_2") (pintype "passive"))
      (node (ref "J1") (pin "18") (pinfunction "18_18") (pintype "bidirectional"))
    )
    (net (code "33") (name "Net-(EPD_C7-Pad2)") (class "Default")
      (node (ref "EPD_C7") (pin "2") (pinfunction "2_2") (pintype "passive"))
      (node (ref "J1") (pin "19") (pinfunction "19_19") (pintype "bidirectional"))
    )
    (net (code "34") (name "Net-(EPD_C8-Pad2)") (class "Default")
      (node (ref "EPD_C8") (pin "2") (pinfunction "2_2") (pintype "passive"))
      (node (ref "J1") (pin "20") (pinfunction "20_20") (pintype "bidirectional"))
    )
    (net (code "35") (name "Net-(EPD_C9-Pad2)") (class "Default")
      (node (ref "EPD_C9") (pin "2") (pinfunction "2_2") (pintype "passive"))
      (node (ref "J1") (pin "21") (pinfunction "21_21") (pintype "bidirectional"))
    )
    (net (code "36") (name "Net-(EPD_C10-Pad2)") (class "Default")
      (node (ref "EPD_C10") (pin "2") (pinfunction "2_2") (pintype "passive"))
      (node (ref "J1") (pin "22") (pinfunction "22_22") (pintype "bidirectional"))
    )
    (net (code "37") (name "Net-(EPD_C11-Pad2)") (class "Default")
      (node (ref "EPD_C11") (pin "2") (pinfunction "2_2") (pintype "passive"))
      (node (ref "J1") (pin "23") (pinfunction "23_23") (pintype "bidirectional"))
    )
    (net (code "38") (name "Net-(EPD_C12-Pad2)") (class "Default")
      (node (ref "EPD_C12") (pin "2") (pinfunction "2_2") (pintype "passive"))
      (node (ref "J1") (pin "24") (pinfunction "24_24") (pintype "bidirectional"))
    )
    (net (code "39") (name "Net-(IC1-CT)") (class "Default")
      (node (ref "C_DELAY") (pin "1") (pinfunction "1_1") (pintype "passive"))
      (node (ref "IC1") (pin "5") (pinfunction "CT_5") (pintype "bidirectional"))
    )
    (net (code "40") (name "Net-(J2-PadA5)") (class "Default")
      (node (ref "J2") (pin "A5") (pinfunction "A5_A5") (pintype "bidirectional"))
      (node (ref "R2-USB1") (pin "2") (pinfunction "2_2") (pintype "passive"))
    )
    (net (code "41") (name "Net-(J2-PadB5)") (class "Default")
      (node (ref "J2") (pin "B5") (pinfunction "B5_B5") (pintype "bidirectional"))
      (node (ref "R2-USB") (pin "1") (pinfunction "1_1") (pintype "passive"))
    )
    (net (code "42") (name "Net-(MCP73831-PROG)") (class "Default")
      (node (ref "MCP73831") (pin "5") (pinfunction "PROG_5") (pintype "input"))
      (node (ref "R2_BAT") (pin "2") (pinfunction "2_2") (pintype "passive"))
    )
    (net (code "43") (name "Net-(MCP73831-STAT)") (class "Default")
      (node (ref "MCP73831") (pin "1") (pinfunction "STAT_1") (pintype "output"))
      (node (ref "R1_BAT") (pin "2") (pinfunction "2_2") (pintype "passive"))
    )
    (net (code "44") (name "PREVGH") (class "Default")
      (node (ref "D5") (pin "1") (pinfunction "K_1") (pintype "bidirectional"))
    )
    (net (code "45") (name "PREVGL") (class "Default")
      (node (ref "D3") (pin "2") (pinfunction "A_2") (pintype "bidirectional"))
    )
    (net (code "46") (name "RESE") (class "Default")
      (node (ref "J1") (pin "3") (pinfunction "3_3") (pintype "bidirectional"))
      (node (ref "Q3") (pin "2") (pinfunction "S_2") (pintype "bidirectional"))
      (node (ref "R3") (pin "2") (pinfunction "2_2") (pintype "passive"))
    )
    (net (code "47") (name "RESE'") (class "Default")
      (node (ref "R2") (pin "2") (pinfunction "2_2") (pintype "passive"))
      (node (ref "R3") (pin "1") (pinfunction "1_1") (pintype "passive"))
      (node (ref "SJ1") (pin "2") (pinfunction "2_2") (pintype "passive"))
    )
    (net (code "48") (name "RESET") (class "Default")
      (node (ref "C5") (pin "1") (pinfunction "1_1") (pintype "passive"))
      (node (ref "IC1") (pin "1") (pinfunction "VOUT_1") (pintype "bidirectional"))
      (node (ref "RESET_BUTTON") (pin "3") (pinfunction "3_3") (pintype "passive"))
      (node (ref "RESET_BUTTON") (pin "4") (pinfunction "4_4") (pintype "passive"))
      (node (ref "R_RESET") (pin "2") (pinfunction "2_2") (pintype "passive"))
      (node (ref "U2") (pin "3") (pinfunction "EN_3") (pintype "input"))
    )
    (net (code "49") (name "RTC_RST") (class "Default")
      (node (ref "U2") (pin "16") (pinfunction "IO18_16") (pintype "bidirectional"))
      (node (ref "U3") (pin "4") (pinfunction "~{RST}_4") (pintype "input"))
    )
    (net (code "50") (name "RX") (class "Default")
      (node (ref "TP2") (pin "TP") (pinfunction "TP_TP") (pintype "input"))
      (node (ref "U2") (pin "24") (pinfunction "RXD0/GPIO17_24") (pintype "bidirectional"))
    )
    (net (code "51") (name "SCK") (class "Default")
      (node (ref "J1") (pin "13") (pinfunction "13_13") (pintype "bidirectional"))
      (node (ref "J4") (pin "P5") (pinfunction "CLK_P5") (pintype "bidirectional"))
      (node (ref "TP8") (pin "TP") (pinfunction "TP_TP") (pintype "input"))
      (node (ref "U1") (pin "6") (pinfunction "CLK_6") (pintype "input"))
      (node (ref "U2") (pin "6") (pinfunction "IO6_6") (pintype "bidirectional"))
    )
    (net (code "52") (name "SCL") (class "Default")
      (node (ref "J3") (pin "1") (pinfunction "1_1") (pintype "power_in"))
      (node (ref "R2_PINH") (pin "1") (pinfunction "1_1") (pintype "passive"))
      (node (ref "SENSOR2") (pin "4") (pinfunction "SCK_4") (pintype "input"))
      (node (ref "U2") (pin "20") (pinfunction "IO22_20") (pintype "bidirectional"))
      (node (ref "U3") (pin "16") (pinfunction "SCL_16") (pintype "input"))
      (node (ref "U4") (pin "7") (pinfunction "SCL_7") (pintype "input"))
    )
    (net (code "53") (name "SDA") (class "Default")
      (node (ref "J3") (pin "2") (pinfunction "2_2") (pintype "power_in"))
      (node (ref "R1_PINH") (pin "1") (pinfunction "1_1") (pintype "passive"))
      (node (ref "SENSOR2") (pin "3") (pinfunction "SDI_3") (pintype "bidirectional"))
      (node (ref "U2") (pin "19") (pinfunction "IO21_19") (pintype "bidirectional"))
      (node (ref "U3") (pin "15") (pinfunction "SDA_15") (pintype "bidirectional"))
      (node (ref "U4") (pin "8") (pinfunction "SDA_8") (pintype "bidirectional"))
    )
    (net (code "54") (name "SRC") (class "Default")
      (node (ref "C4") (pin "2") (pinfunction "2_2") (pintype "passive"))
      (node (ref "D5") (pin "2") (pinfunction "A_2") (pintype "bidirectional"))
      (node (ref "L1") (pin "1") (pinfunction "1_1") (pintype "passive"))
      (node (ref "Q3") (pin "3") (pinfunction "D_3") (pintype "bidirectional"))
    )
    (net (code "55") (name "SS_SD") (class "Default")
      (node (ref "J4") (pin "P2") (pinfunction "CD/DAT3_P2") (pintype "bidirectional"))
      (node (ref "U2") (pin "4") (pinfunction "IO4_4") (pintype "bidirectional"))
    )
    (net (code "56") (name "TX") (class "Default")
      (node (ref "TP1") (pin "TP") (pinfunction "TP_TP") (pintype "input"))
      (node (ref "U2") (pin "25") (pinfunction "TXD0/GPIO16_25") (pintype "bidirectional"))
    )
    (net (code "57") (name "USB_D+") (class "Default")
      (node (ref "D1") (pin "1") (pinfunction "I/O1_1_1") (pintype "bidirectional"))
      (node (ref "U2") (pin "14") (pinfunction "IO13_14") (pintype "bidirectional"))
    )
    (net (code "58") (name "USB_D-") (class "Default")
      (node (ref "D1") (pin "3") (pinfunction "I/O2_1_3") (pintype "bidirectional"))
      (node (ref "U2") (pin "13") (pinfunction "IO12_13") (pintype "bidirectional"))
    )
    (net (code "59") (name "VBAT") (class "Default")
      (node (ref "C2_BAT") (pin "1") (pinfunction "1_1") (pintype "passive"))
      (node (ref "MCP73831") (pin "3") (pinfunction "VBAT_3") (pintype "power_in"))
      (node (ref "Q1") (pin "3") (pinfunction "D_3") (pintype "bidirectional"))
      (node (ref "TP3") (pin "TP") (pinfunction "TP_TP") (pintype "input"))
      (node (ref "U4") (pin "2") (pinfunction "CELL_2") (pintype "power_in"))
      (node (ref "U4") (pin "3") (pinfunction "VDD_3") (pintype "power_in"))
    )
    (net (code "60") (name "VBUS") (class "Default")
      (node (ref "C1_BAT") (pin "1") (pinfunction "1_1") (pintype "passive"))
      (node (ref "C4_USB") (pin "1") (pinfunction "1_1") (pintype "passive"))
      (node (ref "C5_USB") (pin "1") (pinfunction "1_1") (pintype "passive"))
      (node (ref "CHG_LED") (pin "A") (pinfunction "A_A") (pintype "passive"))
      (node (ref "D1") (pin "5") (pinfunction "VBUS_5") (pintype "bidirectional"))
      (node (ref "D2") (pin "2") (pinfunction "ANODE_2") (pintype "bidirectional"))
      (node (ref "MCP73831") (pin "4") (pinfunction "VIN_4") (pintype "power_in"))
      (node (ref "PFMF.050.1") (pin "2") (pinfunction "2_2") (pintype "passive"))
      (node (ref "Q1") (pin "1") (pinfunction "G_1") (pintype "bidirectional"))
      (node (ref "R1_PWRUSB") (pin "2") (pinfunction "2_2") (pintype "passive"))
      (node (ref "TP14") (pin "TP") (pinfunction "TP_TP") (pintype "input"))
    )
    (net (code "61") (name "VRTC") (class "Default")
      (node (ref "C10_SUPERCAP") (pin "1") (pinfunction "1_1") (pintype "passive"))
      (node (ref "C8") (pin "1") (pinfunction "1_1") (pintype "passive"))
      (node (ref "R_CAPACITOR") (pin "2") (pinfunction "2_2") (pintype "passive"))
      (node (ref "U3") (pin "14") (pinfunction "VBAT_14") (pintype "power_in"))
    )
    (net (code "62") (name "VUSB") (class "Default")
      (node (ref "J2") (pin "A4") (pinfunction "A4_A4") (pintype "bidirectional"))
      (node (ref "J2") (pin "A9") (pinfunction "A9_A9") (pintype "bidirectional"))
      (node (ref "J2") (pin "B4") (pinfunction "B4_B4") (pintype "bidirectional"))
      (node (ref "J2") (pin "B9") (pinfunction "B9_B9") (pintype "bidirectional"))
      (node (ref "PFMF.050.1") (pin "1") (pinfunction "1_1") (pintype "passive"))
    )
    (net (code "63") (name "unconnected-(C7-Pad2)") (class "Default")
      (node (ref "C7") (pin "2") (pinfunction "2_2") (pintype "passive"))
    )
    (net (code "64") (name "unconnected-(D6-Pad2)") (class "Default")
      (node (ref "D6") (pin "2") (pinfunction "2_2") (pintype "passive"))
    )
    (net (code "65") (name "unconnected-(D9-Pad2)") (class "Default")
      (node (ref "D9") (pin "2") (pinfunction "2_2") (pintype "passive"))
    )
    (net (code "66") (name "unconnected-(D10-Pad2)") (class "Default")
      (node (ref "D10") (pin "2") (pinfunction "2_2") (pintype "passive"))
    )
    (net (code "67") (name "unconnected-(D11-Pad2)") (class "Default")
      (node (ref "D11") (pin "2") (pinfunction "2_2") (pintype "passive"))
    )
    (net (code "68") (name "unconnected-(IC1-NC-Pad4)") (class "Default")
      (node (ref "IC1") (pin "4") (pinfunction "NC_4") (pintype "no_connect"))
    )
    (net (code "69") (name "unconnected-(IC4-NC-Pad4)") (class "Default")
      (node (ref "IC4") (pin "4") (pinfunction "NC_4") (pintype "no_connect"))
    )
    (net (code "70") (name "unconnected-(J1-Pad1)") (class "Default")
      (node (ref "J1") (pin "1") (pinfunction "1_1") (pintype "bidirectional"))
    )
    (net (code "71") (name "unconnected-(J1-Pad6)") (class "Default")
      (node (ref "J1") (pin "6") (pinfunction "6_6") (pintype "bidirectional"))
    )
    (net (code "72") (name "unconnected-(J1-Pad7)") (class "Default")
      (node (ref "J1") (pin "7") (pinfunction "7_7") (pintype "bidirectional"))
    )
    (net (code "73") (name "unconnected-(J2-PadA8)") (class "Default")
      (node (ref "J2") (pin "A8") (pinfunction "A8_A8") (pintype "bidirectional"))
    )
    (net (code "74") (name "unconnected-(J2-PadB8)") (class "Default")
      (node (ref "J2") (pin "B8") (pinfunction "B8_B8") (pintype "bidirectional"))
    )
    (net (code "75") (name "unconnected-(J4-DAT1-PadP8)") (class "Default")
      (node (ref "J4") (pin "P8") (pinfunction "DAT1_P8") (pintype "bidirectional"))
    )
    (net (code "76") (name "unconnected-(J4-DAT2-PadP1)") (class "Default")
      (node (ref "J4") (pin "P1") (pinfunction "DAT2_P1") (pintype "bidirectional"))
    )
    (net (code "77") (name "unconnected-(J4-DETECTION_1-PadS1)") (class "Default")
      (node (ref "J4") (pin "S1") (pinfunction "DETECTION_1_S1") (pintype "bidirectional"))
    )
    (net (code "78") (name "unconnected-(J4-DETECTION_2-PadS2)") (class "Default")
      (node (ref "J4") (pin "S2") (pinfunction "DETECTION_2_S2") (pintype "bidirectional"))
    )
    (net (code "79") (name "unconnected-(R5-Pad1)") (class "Default")
      (node (ref "R5") (pin "1") (pinfunction "1_1") (pintype "passive"))
    )
    (net (code "80") (name "unconnected-(R6-Pad1)") (class "Default")
      (node (ref "R6") (pin "1") (pinfunction "1_1") (pintype "passive"))
    )
    (net (code "81") (name "unconnected-(R7-Pad1)") (class "Default")
      (node (ref "R7") (pin "1") (pinfunction "1_1") (pintype "passive"))
    )
    (net (code "82") (name "unconnected-(R9-Pad1)") (class "Default")
      (node (ref "R9") (pin "1") (pinfunction "1_1") (pintype "passive"))
    )
    (net (code "83") (name "unconnected-(U2-NC-Pad22)") (class "Default")
      (node (ref "U2") (pin "22") (pinfunction "NC_22") (pintype "no_connect"))
    )
    (net (code "84") (name "unconnected-(U4-~{ALERT}-Pad5)") (class "Default")
      (node (ref "U4") (pin "5") (pinfunction "~{ALERT}_5") (pintype "output"))
    )
  )
)
